# MCU.net
KiCad netlist of a schematic drawn in EAGLE
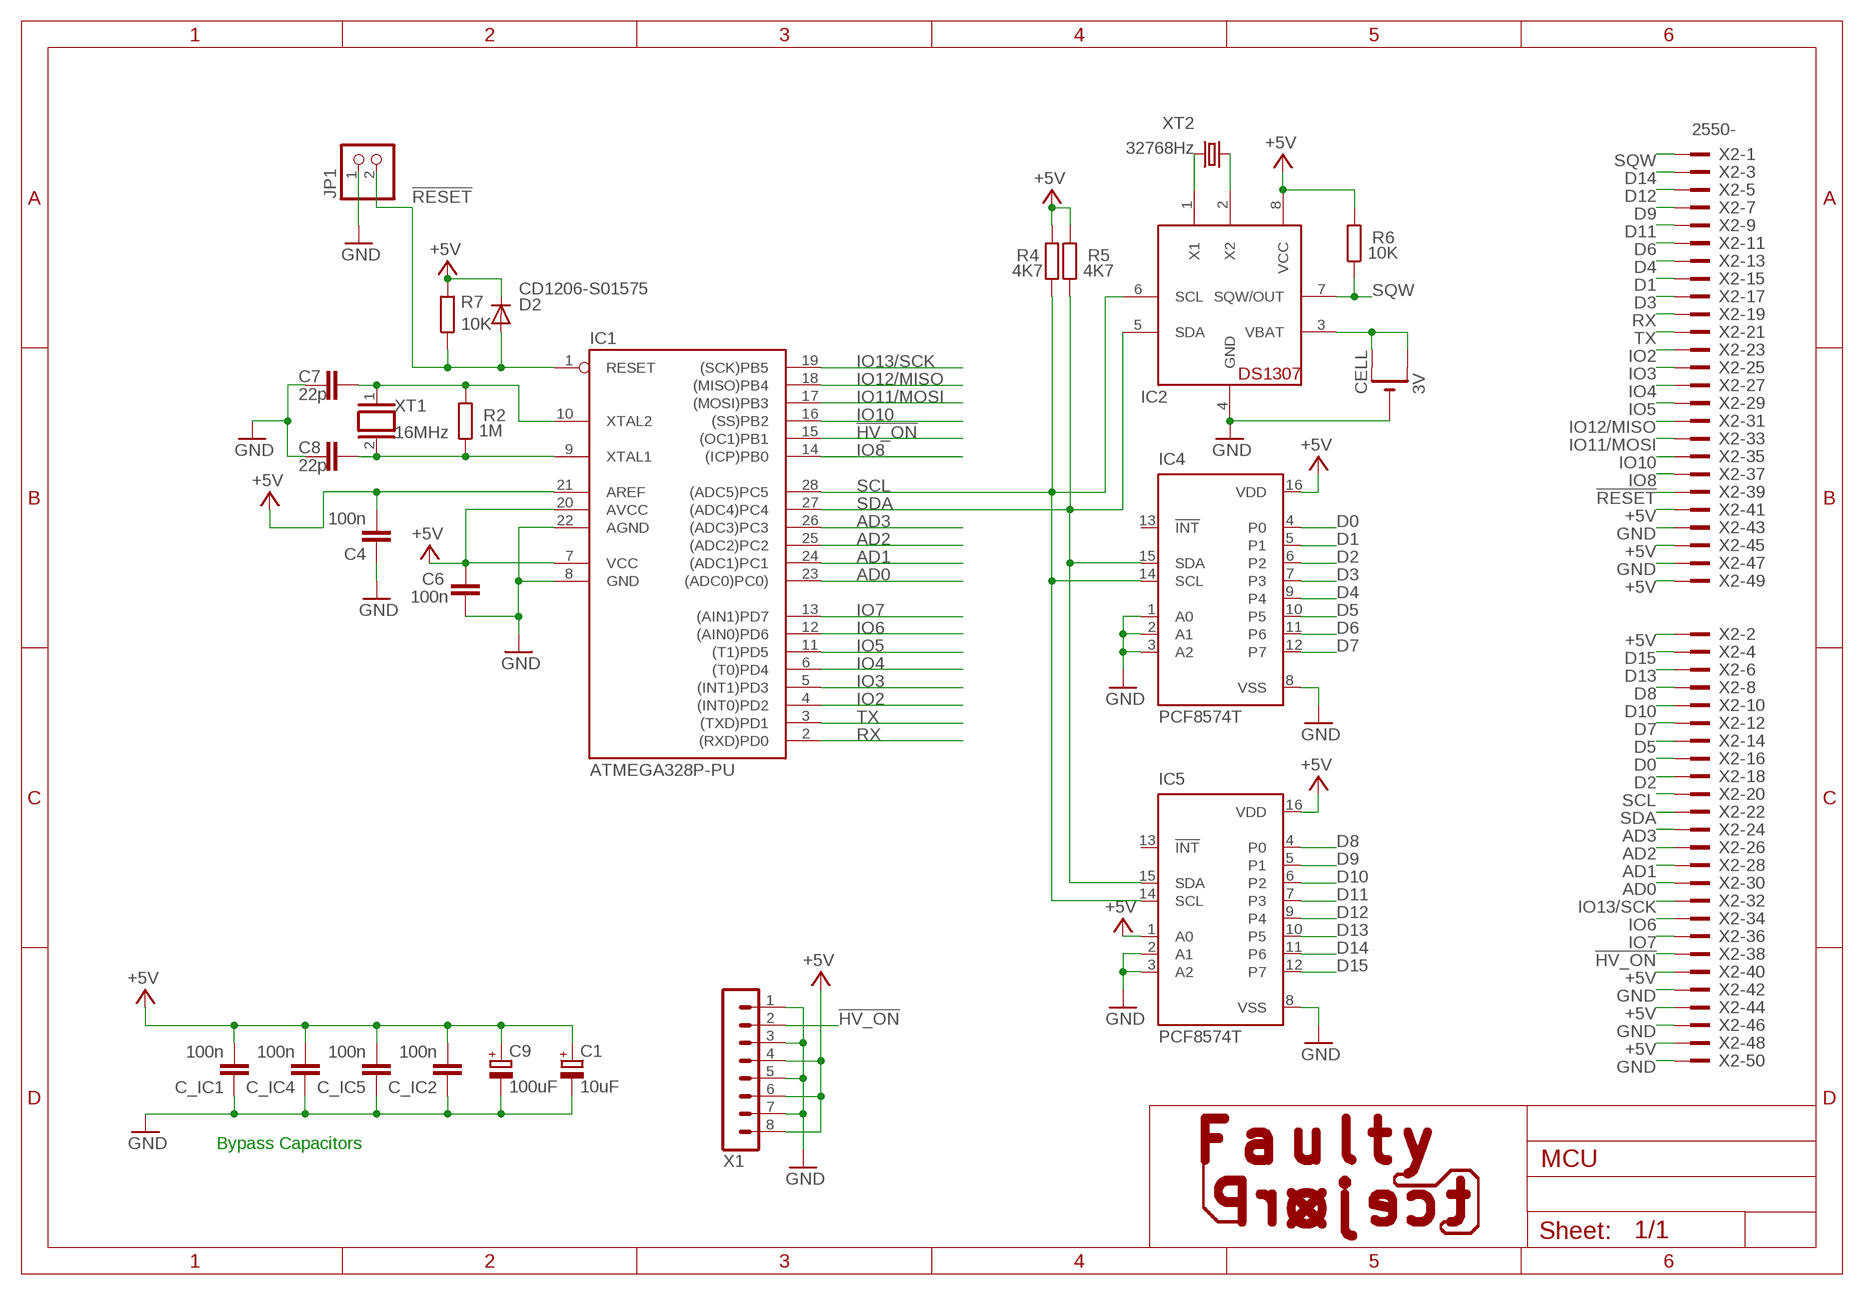
[diagram p0: schematic, sheet 1]

(export (version "E")
  (design (tool "Eeschema 10.0.6"))
  (components
    (comp (ref "C1")
      (value "10uF")
      (footprint "eagle-import:085CS_1AR")
      (libsource (lib "eagle-import") (part "CPOL-EU085CS-1AR"))
    )
    (comp (ref "C4")
      (value "100n")
      (footprint "eagle-import:C1206")
      (libsource (lib "eagle-import") (part "C-EUC1206"))
    )
    (comp (ref "C6")
      (value "100n")
      (footprint "eagle-import:C1206")
      (libsource (lib "eagle-import") (part "C-EUC1206"))
    )
    (comp (ref "C7")
      (value "22p")
      (footprint "eagle-import:C1206")
      (libsource (lib "eagle-import") (part "C-EUC1206"))
    )
    (comp (ref "C8")
      (value "22p")
      (footprint "eagle-import:C1206")
      (libsource (lib "eagle-import") (part "C-EUC1206"))
    )
    (comp (ref "C9")
      (value "100uF")
      (footprint "eagle-import:E5-10,5")
      (libsource (lib "eagle-import") (part "CPOL-EUE5-10.5"))
    )
    (comp (ref "CELL")
      (value "3V")
      (footprint "eagle-import:CR2032-THRU")
      (libsource (lib "eagle-import") (part "CR2032THM"))
    )
    (comp (ref "C_IC1")
      (value "100n")
      (footprint "eagle-import:C1206")
      (libsource (lib "eagle-import") (part "C-EUC1206"))
    )
    (comp (ref "C_IC2")
      (value "100n")
      (footprint "eagle-import:C1206")
      (libsource (lib "eagle-import") (part "C-EUC1206"))
    )
    (comp (ref "C_IC4")
      (value "100n")
      (footprint "eagle-import:C1206")
      (libsource (lib "eagle-import") (part "C-EUC1206"))
    )
    (comp (ref "C_IC5")
      (value "100n")
      (footprint "eagle-import:C1206")
      (libsource (lib "eagle-import") (part "C-EUC1206"))
    )
    (comp (ref "D2")
      (value "CD1206-S01575")
      (footprint "eagle-import:DO41-10")
      (libsource (lib "eagle-import") (part "1N4004"))
    )
    (comp (ref "IC1")
      (value "ATMEGA328P-PU")
      (footprint "eagle-import:DIL28-3")
      (libsource (lib "eagle-import") (part "ATMEGA328P-PU"))
    )
    (comp (ref "IC2")
      (value "DS1307")
      (footprint "eagle-import:DIL08")
      (libsource (lib "eagle-import") (part "DS1307"))
    )
    (comp (ref "IC4")
      (value "PCF8574T")
      (footprint "eagle-import:SO16W")
      (fields (field (name "MPN") "PCF8574T/3,512"))
      (libsource (lib "eagle-import") (part "PCF8574T"))
    )
    (comp (ref "IC5")
      (value "PCF8574T")
      (footprint "eagle-import:SO16W")
      (fields (field (name "MPN") "PCF8574T/3,512"))
      (libsource (lib "eagle-import") (part "PCF8574T"))
    )
    (comp (ref "JP1")
      (value "PINHD-1X2")
      (footprint "eagle-import:1X02")
      (libsource (lib "eagle-import") (part "PINHD-1X2"))
    )
    (comp (ref "R2")
      (value "1M")
      (footprint "eagle-import:M1206")
      (libsource (lib "eagle-import") (part "R-EU_M1206"))
    )
    (comp (ref "R4")
      (value "4K7")
      (footprint "eagle-import:M1206")
      (libsource (lib "eagle-import") (part "R-EU_M1206"))
    )
    (comp (ref "R5")
      (value "4K7")
      (footprint "eagle-import:M1206")
      (libsource (lib "eagle-import") (part "R-EU_M1206"))
    )
    (comp (ref "R6")
      (value "10K")
      (footprint "eagle-import:M1206")
      (libsource (lib "eagle-import") (part "R-EU_M1206"))
    )
    (comp (ref "R7")
      (value "10K")
      (footprint "eagle-import:M1206")
      (libsource (lib "eagle-import") (part "R-EU_M1206"))
    )
    (comp (ref "X1")
      (value "MA08-1W")
      (footprint "eagle-import:MA08-1W")
      (libsource (lib "eagle-import") (part "MA08-1W"))
    )
    (comp (ref "X2")
      (value "2550-")
      (footprint "eagle-import:PAK100_2500-50")
      (libsource (lib "eagle-import") (part "2550-"))
    )
    (comp (ref "XT1")
      (value "16MHz")
      (footprint "eagle-import:QS")
      (libsource (lib "eagle-import") (part "XTAL/S"))
    )
    (comp (ref "XT2")
      (value "32768Hz")
      (footprint "eagle-import:TC26H")
      (libsource (lib "eagle-import") (part "CRYSTALTC26H"))
    )
  )
  (nets
    (net (code "1") (name "+5V") (class "Default")
      (node (ref "C1") (pin "+") (pinfunction "+_+") (pintype "passive"))
      (node (ref "C4") (pin "2") (pinfunction "2_2") (pintype "passive"))
      (node (ref "C6") (pin "2") (pinfunction "2_2") (pintype "passive"))
      (node (ref "C9") (pin "+") (pinfunction "+_+") (pintype "passive"))
      (node (ref "C_IC1") (pin "2") (pinfunction "2_2") (pintype "passive"))
      (node (ref "C_IC2") (pin "2") (pinfunction "2_2") (pintype "passive"))
      (node (ref "C_IC4") (pin "2") (pinfunction "2_2") (pintype "passive"))
      (node (ref "C_IC5") (pin "2") (pinfunction "2_2") (pintype "passive"))
      (node (ref "D2") (pin "C") (pinfunction "C_C") (pintype "passive"))
      (node (ref "IC1") (pin "20") (pinfunction "AVCC_20") (pintype "power_in"))
      (node (ref "IC1") (pin "21") (pinfunction "AREF_21") (pintype "passive"))
      (node (ref "IC1") (pin "7") (pinfunction "VCC_7") (pintype "power_in"))
      (node (ref "IC2") (pin "8") (pinfunction "VCC_8") (pintype "power_in"))
      (node (ref "IC4") (pin "16") (pinfunction "VDD_16") (pintype "power_in"))
      (node (ref "IC5") (pin "1") (pinfunction "A0_1") (pintype "input"))
      (node (ref "IC5") (pin "16") (pinfunction "VDD_16") (pintype "power_in"))
      (node (ref "R4") (pin "2") (pinfunction "2_2") (pintype "passive"))
      (node (ref "R5") (pin "2") (pinfunction "2_2") (pintype "passive"))
      (node (ref "R6") (pin "2") (pinfunction "2_2") (pintype "passive"))
      (node (ref "R7") (pin "2") (pinfunction "2_2") (pintype "passive"))
      (node (ref "X1") (pin "4") (pinfunction "4_4") (pintype "passive"))
      (node (ref "X1") (pin "6") (pinfunction "6_6") (pintype "passive"))
      (node (ref "X1") (pin "8") (pinfunction "8_8") (pintype "passive"))
      (node (ref "X2") (pin "2") (pinfunction "KL_2") (pintype "passive"))
      (node (ref "X2") (pin "40") (pinfunction "KL_40") (pintype "passive"))
      (node (ref "X2") (pin "41") (pinfunction "KL_41") (pintype "passive"))
      (node (ref "X2") (pin "44") (pinfunction "KL_44") (pintype "passive"))
      (node (ref "X2") (pin "45") (pinfunction "KL_45") (pintype "passive"))
      (node (ref "X2") (pin "48") (pinfunction "KL_48") (pintype "passive"))
      (node (ref "X2") (pin "49") (pinfunction "KL_49") (pintype "passive"))
    )
    (net (code "2") (name "/AD0") (class "Default")
      (node (ref "IC1") (pin "23") (pinfunction "(ADC0)PC0)_23") (pintype "bidirectional"))
      (node (ref "X2") (pin "30") (pinfunction "KL_30") (pintype "passive"))
    )
    (net (code "3") (name "/AD1") (class "Default")
      (node (ref "IC1") (pin "24") (pinfunction "(ADC1)PC1_24") (pintype "bidirectional"))
      (node (ref "X2") (pin "28") (pinfunction "KL_28") (pintype "passive"))
    )
    (net (code "4") (name "/AD2") (class "Default")
      (node (ref "IC1") (pin "25") (pinfunction "(ADC2)PC2_25") (pintype "bidirectional"))
      (node (ref "X2") (pin "26") (pinfunction "KL_26") (pintype "passive"))
    )
    (net (code "5") (name "/AD3") (class "Default")
      (node (ref "IC1") (pin "26") (pinfunction "(ADC3)PC3_26") (pintype "bidirectional"))
      (node (ref "X2") (pin "24") (pinfunction "KL_24") (pintype "passive"))
    )
    (net (code "6") (name "/D0") (class "Default")
      (node (ref "IC4") (pin "4") (pinfunction "P0_4") (pintype "bidirectional"))
      (node (ref "X2") (pin "16") (pinfunction "KL_16") (pintype "passive"))
    )
    (net (code "7") (name "/D1") (class "Default")
      (node (ref "IC4") (pin "5") (pinfunction "P1_5") (pintype "bidirectional"))
      (node (ref "X2") (pin "15") (pinfunction "KL_15") (pintype "passive"))
    )
    (net (code "8") (name "/D2") (class "Default")
      (node (ref "IC4") (pin "6") (pinfunction "P2_6") (pintype "bidirectional"))
      (node (ref "X2") (pin "18") (pinfunction "KL_18") (pintype "passive"))
    )
    (net (code "9") (name "/D3") (class "Default")
      (node (ref "IC4") (pin "7") (pinfunction "P3_7") (pintype "bidirectional"))
      (node (ref "X2") (pin "17") (pinfunction "KL_17") (pintype "passive"))
    )
    (net (code "10") (name "/D4") (class "Default")
      (node (ref "IC4") (pin "9") (pinfunction "P4_9") (pintype "bidirectional"))
      (node (ref "X2") (pin "13") (pinfunction "KL_13") (pintype "passive"))
    )
    (net (code "11") (name "/D5") (class "Default")
      (node (ref "IC4") (pin "10") (pinfunction "P5_10") (pintype "bidirectional"))
      (node (ref "X2") (pin "14") (pinfunction "KL_14") (pintype "passive"))
    )
    (net (code "12") (name "/D6") (class "Default")
      (node (ref "IC4") (pin "11") (pinfunction "P6_11") (pintype "bidirectional"))
      (node (ref "X2") (pin "11") (pinfunction "KL_11") (pintype "passive"))
    )
    (net (code "13") (name "/D7") (class "Default")
      (node (ref "IC4") (pin "12") (pinfunction "P7_12") (pintype "bidirectional"))
      (node (ref "X2") (pin "12") (pinfunction "KL_12") (pintype "passive"))
    )
    (net (code "14") (name "/D8") (class "Default")
      (node (ref "IC5") (pin "4") (pinfunction "P0_4") (pintype "bidirectional"))
      (node (ref "X2") (pin "8") (pinfunction "KL_8") (pintype "passive"))
    )
    (net (code "15") (name "/D9") (class "Default")
      (node (ref "IC5") (pin "5") (pinfunction "P1_5") (pintype "bidirectional"))
      (node (ref "X2") (pin "7") (pinfunction "KL_7") (pintype "passive"))
    )
    (net (code "16") (name "/D10") (class "Default")
      (node (ref "IC5") (pin "6") (pinfunction "P2_6") (pintype "bidirectional"))
      (node (ref "X2") (pin "10") (pinfunction "KL_10") (pintype "passive"))
    )
    (net (code "17") (name "/D11") (class "Default")
      (node (ref "IC5") (pin "7") (pinfunction "P3_7") (pintype "bidirectional"))
      (node (ref "X2") (pin "9") (pinfunction "KL_9") (pintype "passive"))
    )
    (net (code "18") (name "/D12") (class "Default")
      (node (ref "IC5") (pin "9") (pinfunction "P4_9") (pintype "bidirectional"))
      (node (ref "X2") (pin "5") (pinfunction "KL_5") (pintype "passive"))
    )
    (net (code "19") (name "/D13") (class "Default")
      (node (ref "IC5") (pin "10") (pinfunction "P5_10") (pintype "bidirectional"))
      (node (ref "X2") (pin "6") (pinfunction "KL_6") (pintype "passive"))
    )
    (net (code "20") (name "/D14") (class "Default")
      (node (ref "IC5") (pin "11") (pinfunction "P6_11") (pintype "bidirectional"))
      (node (ref "X2") (pin "3") (pinfunction "KL_3") (pintype "passive"))
    )
    (net (code "21") (name "/D15") (class "Default")
      (node (ref "IC5") (pin "12") (pinfunction "P7_12") (pintype "bidirectional"))
      (node (ref "X2") (pin "4") (pinfunction "KL_4") (pintype "passive"))
    )
    (net (code "22") (name "/IO2") (class "Default")
      (node (ref "IC1") (pin "4") (pinfunction "(INT0)PD2_4") (pintype "bidirectional"))
      (node (ref "X2") (pin "23") (pinfunction "KL_23") (pintype "passive"))
    )
    (net (code "23") (name "/IO3") (class "Default")
      (node (ref "IC1") (pin "5") (pinfunction "(INT1)PD3_5") (pintype "bidirectional"))
      (node (ref "X2") (pin "25") (pinfunction "KL_25") (pintype "passive"))
    )
    (net (code "24") (name "/IO4") (class "Default")
      (node (ref "IC1") (pin "6") (pinfunction "(T0)PD4_6") (pintype "bidirectional"))
      (node (ref "X2") (pin "27") (pinfunction "KL_27") (pintype "passive"))
    )
    (net (code "25") (name "/IO5") (class "Default")
      (node (ref "IC1") (pin "11") (pinfunction "(T1)PD5_11") (pintype "bidirectional"))
      (node (ref "X2") (pin "29") (pinfunction "KL_29") (pintype "passive"))
    )
    (net (code "26") (name "/IO6") (class "Default")
      (node (ref "IC1") (pin "12") (pinfunction "(AIN0)PD6_12") (pintype "bidirectional"))
      (node (ref "X2") (pin "34") (pinfunction "KL_34") (pintype "passive"))
    )
    (net (code "27") (name "/IO7") (class "Default")
      (node (ref "IC1") (pin "13") (pinfunction "(AIN1)PD7_13") (pintype "bidirectional"))
      (node (ref "X2") (pin "36") (pinfunction "KL_36") (pintype "passive"))
    )
    (net (code "28") (name "/IO8") (class "Default")
      (node (ref "IC1") (pin "14") (pinfunction "(ICP)PB0_14") (pintype "bidirectional"))
      (node (ref "X2") (pin "37") (pinfunction "KL_37") (pintype "passive"))
    )
    (net (code "29") (name "/IO10") (class "Default")
      (node (ref "IC1") (pin "16") (pinfunction "(SS)PB2_16") (pintype "bidirectional"))
      (node (ref "X2") (pin "35") (pinfunction "KL_35") (pintype "passive"))
    )
    (net (code "30") (name "/IO11{slash}MOSI") (class "Default")
      (node (ref "IC1") (pin "17") (pinfunction "(MOSI)PB3_17") (pintype "bidirectional"))
      (node (ref "X2") (pin "33") (pinfunction "KL_33") (pintype "passive"))
    )
    (net (code "31") (name "/IO12{slash}MISO") (class "Default")
      (node (ref "IC1") (pin "18") (pinfunction "(MISO)PB4_18") (pintype "bidirectional"))
      (node (ref "X2") (pin "31") (pinfunction "KL_31") (pintype "passive"))
    )
    (net (code "32") (name "/IO13{slash}SCK") (class "Default")
      (node (ref "IC1") (pin "19") (pinfunction "(SCK)PB5_19") (pintype "bidirectional"))
      (node (ref "X2") (pin "32") (pinfunction "KL_32") (pintype "passive"))
    )
    (net (code "33") (name "/RX") (class "Default")
      (node (ref "IC1") (pin "2") (pinfunction "(RXD)PD0_2") (pintype "bidirectional"))
      (node (ref "X2") (pin "19") (pinfunction "KL_19") (pintype "passive"))
    )
    (net (code "34") (name "/SCL") (class "Default")
      (node (ref "IC1") (pin "28") (pinfunction "(ADC5)PC5_28") (pintype "bidirectional"))
      (node (ref "IC2") (pin "6") (pinfunction "SCL_6") (pintype "bidirectional"))
      (node (ref "IC4") (pin "14") (pinfunction "SCL_14") (pintype "input"))
      (node (ref "IC5") (pin "14") (pinfunction "SCL_14") (pintype "input"))
      (node (ref "R4") (pin "1") (pinfunction "1_1") (pintype "passive"))
      (node (ref "X2") (pin "20") (pinfunction "KL_20") (pintype "passive"))
    )
    (net (code "35") (name "/SDA") (class "Default")
      (node (ref "IC1") (pin "27") (pinfunction "(ADC4)PC4_27") (pintype "bidirectional"))
      (node (ref "IC2") (pin "5") (pinfunction "SDA_5") (pintype "bidirectional"))
      (node (ref "IC4") (pin "15") (pinfunction "SDA_15") (pintype "bidirectional"))
      (node (ref "IC5") (pin "15") (pinfunction "SDA_15") (pintype "bidirectional"))
      (node (ref "R5") (pin "1") (pinfunction "1_1") (pintype "passive"))
      (node (ref "X2") (pin "22") (pinfunction "KL_22") (pintype "passive"))
    )
    (net (code "36") (name "/SQW") (class "Default")
      (node (ref "IC2") (pin "7") (pinfunction "SQW/OUT_7") (pintype "bidirectional"))
      (node (ref "R6") (pin "1") (pinfunction "1_1") (pintype "passive"))
      (node (ref "X2") (pin "1") (pinfunction "KL_1") (pintype "passive"))
    )
    (net (code "37") (name "/TX") (class "Default")
      (node (ref "IC1") (pin "3") (pinfunction "(TXD)PD1_3") (pintype "bidirectional"))
      (node (ref "X2") (pin "21") (pinfunction "KL_21") (pintype "passive"))
    )
    (net (code "38") (name "/~{HV_ON}") (class "Default")
      (node (ref "IC1") (pin "15") (pinfunction "(OC1)PB1_15") (pintype "bidirectional"))
      (node (ref "X1") (pin "2") (pinfunction "2_2") (pintype "passive"))
      (node (ref "X2") (pin "38") (pinfunction "KL_38") (pintype "passive"))
    )
    (net (code "39") (name "/~{RESET}") (class "Default")
      (node (ref "D2") (pin "A") (pinfunction "A_A") (pintype "passive"))
      (node (ref "IC1") (pin "1") (pinfunction "RESET_1") (pintype "input"))
      (node (ref "JP1") (pin "2") (pinfunction "2_2") (pintype "passive"))
      (node (ref "R7") (pin "1") (pinfunction "1_1") (pintype "passive"))
      (node (ref "X2") (pin "39") (pinfunction "KL_39") (pintype "passive"))
    )
    (net (code "40") (name "GND") (class "Default")
      (node (ref "C1") (pin "-") (pinfunction "-_-") (pintype "passive"))
      (node (ref "C4") (pin "1") (pinfunction "1_1") (pintype "passive"))
      (node (ref "C6") (pin "1") (pinfunction "1_1") (pintype "passive"))
      (node (ref "C7") (pin "1") (pinfunction "1_1") (pintype "passive"))
      (node (ref "C8") (pin "1") (pinfunction "1_1") (pintype "passive"))
      (node (ref "C9") (pin "-") (pinfunction "-_-") (pintype "passive"))
      (node (ref "CELL") (pin "-") (pinfunction "-_-") (pintype "passive"))
      (node (ref "C_IC1") (pin "1") (pinfunction "1_1") (pintype "passive"))
      (node (ref "C_IC2") (pin "1") (pinfunction "1_1") (pintype "passive"))
      (node (ref "C_IC4") (pin "1") (pinfunction "1_1") (pintype "passive"))
      (node (ref "C_IC5") (pin "1") (pinfunction "1_1") (pintype "passive"))
      (node (ref "IC1") (pin "22") (pinfunction "AGND_22") (pintype "power_in"))
      (node (ref "IC1") (pin "8") (pinfunction "GND_8") (pintype "power_in"))
      (node (ref "IC2") (pin "4") (pinfunction "GND_4") (pintype "power_in"))
      (node (ref "IC4") (pin "1") (pinfunction "A0_1") (pintype "input"))
      (node (ref "IC4") (pin "2") (pinfunction "A1_2") (pintype "input"))
      (node (ref "IC4") (pin "3") (pinfunction "A2_3") (pintype "input"))
      (node (ref "IC4") (pin "8") (pinfunction "VSS_8") (pintype "power_in"))
      (node (ref "IC5") (pin "2") (pinfunction "A1_2") (pintype "input"))
      (node (ref "IC5") (pin "3") (pinfunction "A2_3") (pintype "input"))
      (node (ref "IC5") (pin "8") (pinfunction "VSS_8") (pintype "power_in"))
      (node (ref "JP1") (pin "1") (pinfunction "1_1") (pintype "passive"))
      (node (ref "X1") (pin "1") (pinfunction "1_1") (pintype "passive"))
      (node (ref "X1") (pin "3") (pinfunction "3_3") (pintype "passive"))
      (node (ref "X1") (pin "5") (pinfunction "5_5") (pintype "passive"))
      (node (ref "X1") (pin "7") (pinfunction "7_7") (pintype "passive"))
      (node (ref "X2") (pin "42") (pinfunction "KL_42") (pintype "passive"))
      (node (ref "X2") (pin "43") (pinfunction "KL_43") (pintype "passive"))
      (node (ref "X2") (pin "46") (pinfunction "KL_46") (pintype "passive"))
      (node (ref "X2") (pin "47") (pinfunction "KL_47") (pintype "passive"))
      (node (ref "X2") (pin "50") (pinfunction "KL_50") (pintype "passive"))
    )
    (net (code "41") (name "Net-(CELL-+)") (class "Default")
      (node (ref "CELL") (pin "+1") (pinfunction "+_+1") (pintype "passive"))
      (node (ref "CELL") (pin "+2") (pinfunction "+1_+2") (pintype "passive"))
      (node (ref "IC2") (pin "3") (pinfunction "VBAT_3") (pintype "power_in"))
    )
    (net (code "42") (name "Net-(IC1-XTAL1)") (class "Default")
      (node (ref "C8") (pin "2") (pinfunction "2_2") (pintype "passive"))
      (node (ref "IC1") (pin "9") (pinfunction "XTAL1_9") (pintype "bidirectional"))
      (node (ref "R2") (pin "1") (pinfunction "1_1") (pintype "passive"))
      (node (ref "XT1") (pin "2") (pinfunction "2_2") (pintype "passive"))
    )
    (net (code "43") (name "Net-(IC1-XTAL2)") (class "Default")
      (node (ref "C7") (pin "2") (pinfunction "2_2") (pintype "passive"))
      (node (ref "IC1") (pin "10") (pinfunction "XTAL2_10") (pintype "bidirectional"))
      (node (ref "R2") (pin "2") (pinfunction "2_2") (pintype "passive"))
      (node (ref "XT1") (pin "1") (pinfunction "1_1") (pintype "passive"))
    )
    (net (code "44") (name "Net-(IC2-X1)") (class "Default")
      (node (ref "IC2") (pin "1") (pinfunction "X1_1") (pintype "passive"))
      (node (ref "XT2") (pin "2") (pinfunction "2_2") (pintype "passive"))
    )
    (net (code "45") (name "Net-(IC2-X2)") (class "Default")
      (node (ref "IC2") (pin "2") (pinfunction "X2_2") (pintype "passive"))
      (node (ref "XT2") (pin "1") (pinfunction "1_1") (pintype "passive"))
    )
    (net (code "46") (name "unconnected-(IC4-~{INT}-Pad13)") (class "Default")
      (node (ref "IC4") (pin "13") (pinfunction "~{INT}_13") (pintype "output"))
    )
    (net (code "47") (name "unconnected-(IC5-~{INT}-Pad13)") (class "Default")
      (node (ref "IC5") (pin "13") (pinfunction "~{INT}_13") (pintype "output"))
    )
  )
)
